# res_v2.net
KiCad netlist of a schematic drawn in EAGLE
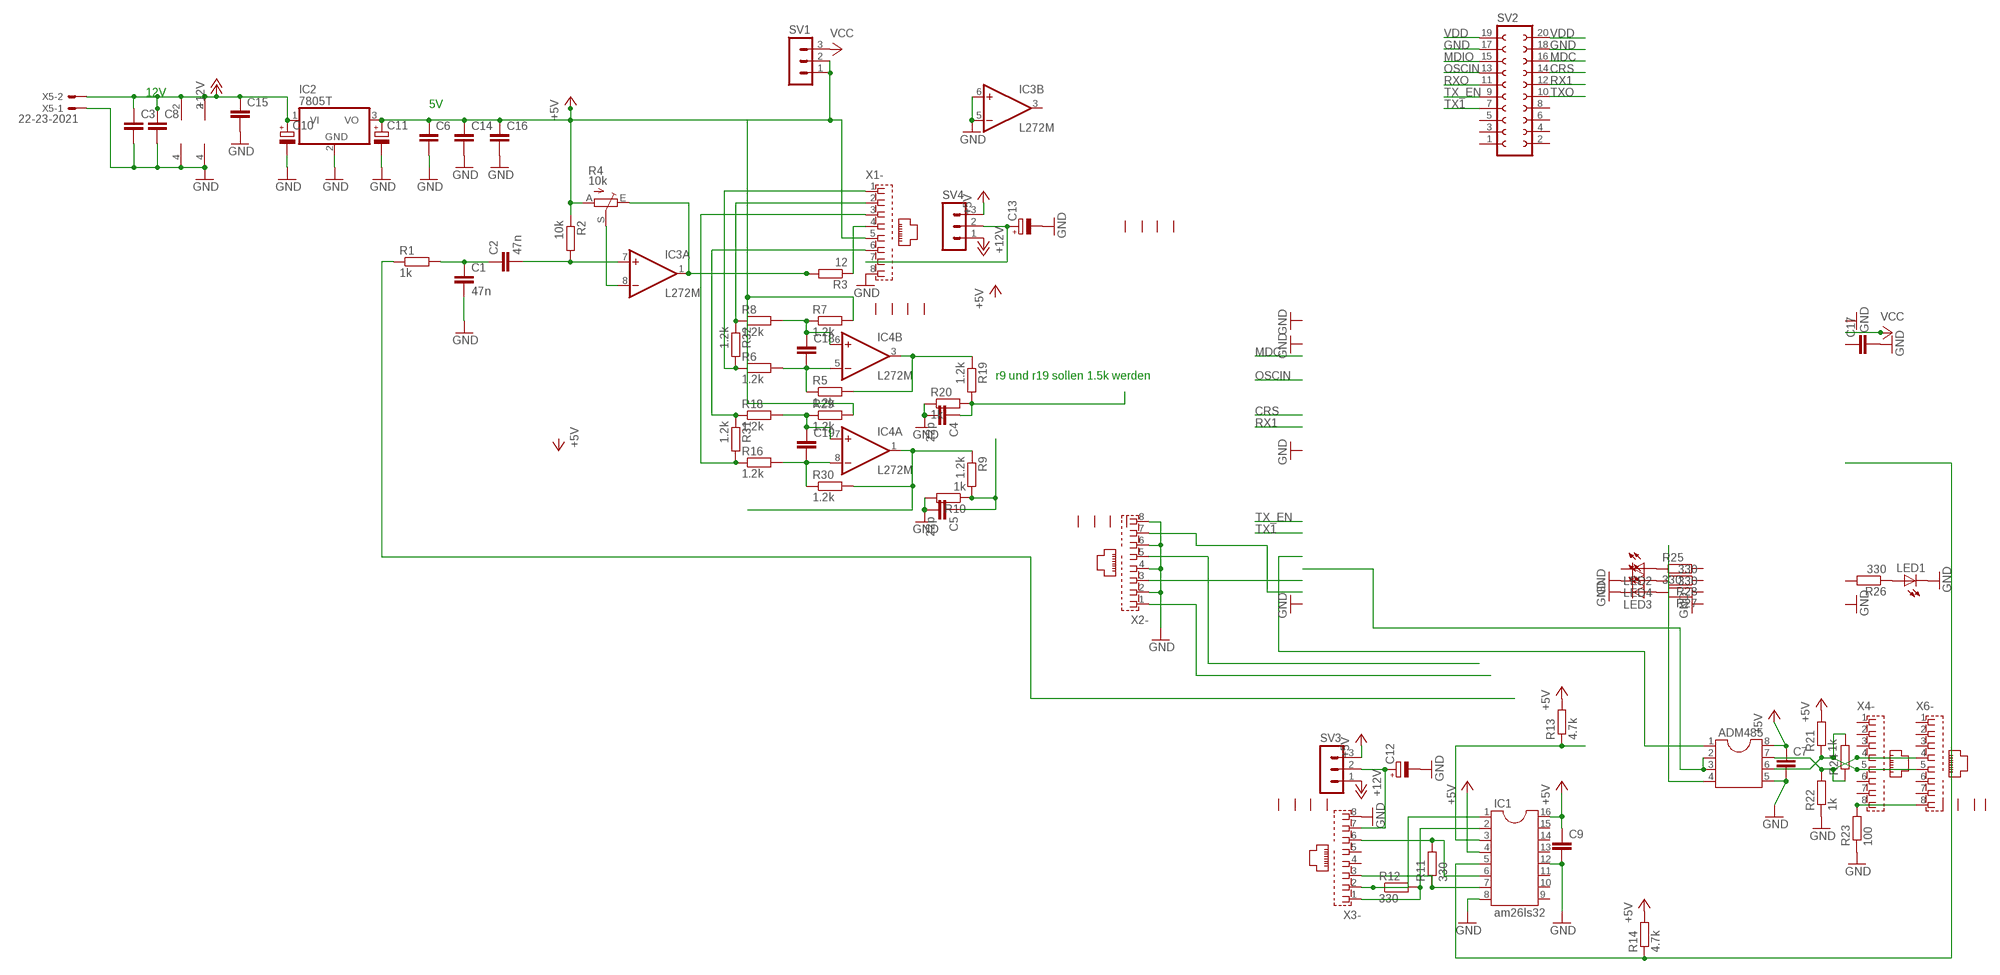
[diagram p0: schematic, sheet 1]

(export (version "E")
  (design (tool "Eeschema 10.0.6"))
  (components
    (comp (ref "ADM485")
      (value "DIL8")
      (footprint "eagle-import:DIL08")
      (libsource (lib "eagle-import") (part "DIL8"))
    )
    (comp (ref "C1")
      (value "47n")
      (footprint "eagle-import:C050-025X075")
      (libsource (lib "eagle-import") (part "C-EU050-025X075"))
    )
    (comp (ref "C2")
      (value "47n")
      (footprint "eagle-import:C050-025X075")
      (libsource (lib "eagle-import") (part "C-EU050-025X075"))
    )
    (comp (ref "C3")
      (value "C-EU050-025X075")
      (footprint "eagle-import:C050-025X075")
      (libsource (lib "eagle-import") (part "C-EU050-025X075"))
    )
    (comp (ref "C4")
      (value "22p")
      (footprint "eagle-import:C050-025X075")
      (libsource (lib "eagle-import") (part "C-EU050-025X075"))
    )
    (comp (ref "C5")
      (value "22p")
      (footprint "eagle-import:C050-025X075")
      (libsource (lib "eagle-import") (part "C-EU050-025X075"))
    )
    (comp (ref "C6")
      (value "C-EU050-025X075")
      (footprint "eagle-import:C050-025X075")
      (libsource (lib "eagle-import") (part "C-EU050-025X075"))
    )
    (comp (ref "C7")
      (value "C-EU050-025X075")
      (footprint "eagle-import:C050-025X075")
      (libsource (lib "eagle-import") (part "C-EU050-025X075"))
    )
    (comp (ref "C8")
      (value "C-EU050-025X075")
      (footprint "eagle-import:C050-025X075")
      (libsource (lib "eagle-import") (part "C-EU050-025X075"))
    )
    (comp (ref "C9")
      (value "C-EU050-025X075")
      (footprint "eagle-import:C050-025X075")
      (libsource (lib "eagle-import") (part "C-EU050-025X075"))
    )
    (comp (ref "C10")
      (value "CPOL-EUE2.5-5")
      (footprint "eagle-import:E2,5-5")
      (libsource (lib "eagle-import") (part "CPOL-EUE2.5-5"))
    )
    (comp (ref "C11")
      (value "CPOL-EUE2.5-5")
      (footprint "eagle-import:E2,5-5")
      (libsource (lib "eagle-import") (part "CPOL-EUE2.5-5"))
    )
    (comp (ref "C12")
      (value "CPOL-EUE2.5-5")
      (footprint "eagle-import:E2,5-5")
      (libsource (lib "eagle-import") (part "CPOL-EUE2.5-5"))
    )
    (comp (ref "C13")
      (value "CPOL-EUE2.5-5")
      (footprint "eagle-import:E2,5-5")
      (libsource (lib "eagle-import") (part "CPOL-EUE2.5-5"))
    )
    (comp (ref "C14")
      (value "C-EU050-025X075")
      (footprint "eagle-import:C050-025X075")
      (libsource (lib "eagle-import") (part "C-EU050-025X075"))
    )
    (comp (ref "C15")
      (value "C-EU050-025X075")
      (footprint "eagle-import:C050-025X075")
      (libsource (lib "eagle-import") (part "C-EU050-025X075"))
    )
    (comp (ref "C16")
      (value "C-EU050-025X075")
      (footprint "eagle-import:C050-025X075")
      (libsource (lib "eagle-import") (part "C-EU050-025X075"))
    )
    (comp (ref "C17")
      (value "C-EU050-025X075")
      (footprint "eagle-import:C050-025X075")
      (libsource (lib "eagle-import") (part "C-EU050-025X075"))
    )
    (comp (ref "C18")
      (value "C-EU050-025X075")
      (footprint "eagle-import:C050-025X075")
      (libsource (lib "eagle-import") (part "C-EU050-025X075"))
    )
    (comp (ref "C19")
      (value "C-EU050-025X075")
      (footprint "eagle-import:C050-025X075")
      (libsource (lib "eagle-import") (part "C-EU050-025X075"))
    )
    (comp (ref "IC1")
      (value "am26ls32")
      (footprint "eagle-import:DIL16")
      (libsource (lib "eagle-import") (part "DIL16"))
    )
    (comp (ref "IC2")
      (value "7805T")
      (footprint "eagle-import:TO220H")
      (libsource (lib "eagle-import") (part "78T05"))
    )
    (comp (ref "IC3")
      (value "L272M")
      (footprint "eagle-import:DIL08")
      (libsource (lib "eagle-import") (part "L272M"))
    )
    (comp (ref "IC4")
      (value "L272M")
      (footprint "eagle-import:DIL08")
      (libsource (lib "eagle-import") (part "L272M"))
    )
    (comp (ref "LED1")
      (value "LED3MM")
      (footprint "eagle-import:LED3MM")
      (libsource (lib "eagle-import") (part "LED3MM"))
    )
    (comp (ref "LED2")
      (value "LED3MM")
      (footprint "eagle-import:LED3MM")
      (libsource (lib "eagle-import") (part "LED3MM"))
    )
    (comp (ref "LED3")
      (value "LED3MM")
      (footprint "eagle-import:LED3MM")
      (libsource (lib "eagle-import") (part "LED3MM"))
    )
    (comp (ref "LED4")
      (value "LED3MM")
      (footprint "eagle-import:LED3MM")
      (libsource (lib "eagle-import") (part "LED3MM"))
    )
    (comp (ref "R1")
      (value "1k")
      (footprint "eagle-import:0204_7")
      (libsource (lib "eagle-import") (part "R-EU_0204/7"))
    )
    (comp (ref "R2")
      (value "10k")
      (footprint "eagle-import:0204_7")
      (libsource (lib "eagle-import") (part "R-EU_0204/7"))
    )
    (comp (ref "R3")
      (value "12")
      (footprint "eagle-import:0204_7")
      (libsource (lib "eagle-import") (part "R-EU_0204/7"))
    )
    (comp (ref "R4")
      (value "10k")
      (footprint "eagle-import:CA6V")
      (libsource (lib "eagle-import") (part "TRIM_EU-CA6V"))
    )
    (comp (ref "R5")
      (value "1.2k")
      (footprint "eagle-import:0204_7")
      (libsource (lib "eagle-import") (part "R-EU_0204/7"))
    )
    (comp (ref "R6")
      (value "1.2k")
      (footprint "eagle-import:0204_7")
      (libsource (lib "eagle-import") (part "R-EU_0204/7"))
    )
    (comp (ref "R7")
      (value "1.2k")
      (footprint "eagle-import:0204_7")
      (libsource (lib "eagle-import") (part "R-EU_0204/7"))
    )
    (comp (ref "R8")
      (value "1.2k")
      (footprint "eagle-import:0204_7")
      (libsource (lib "eagle-import") (part "R-EU_0204/7"))
    )
    (comp (ref "R9")
      (value "1.2k")
      (footprint "eagle-import:0204_7")
      (libsource (lib "eagle-import") (part "R-EU_0204/7"))
    )
    (comp (ref "R10")
      (value "1k")
      (footprint "eagle-import:0204_7")
      (libsource (lib "eagle-import") (part "R-EU_0204/7"))
    )
    (comp (ref "R11")
      (value "330")
      (footprint "eagle-import:0204_7")
      (libsource (lib "eagle-import") (part "R-EU_0204/7"))
    )
    (comp (ref "R12")
      (value "330")
      (footprint "eagle-import:0204_7")
      (libsource (lib "eagle-import") (part "R-EU_0204/7"))
    )
    (comp (ref "R13")
      (value "4.7k")
      (footprint "eagle-import:0204_7")
      (libsource (lib "eagle-import") (part "R-EU_0204/7"))
    )
    (comp (ref "R14")
      (value "4.7k")
      (footprint "eagle-import:0204_7")
      (libsource (lib "eagle-import") (part "R-EU_0204/7"))
    )
    (comp (ref "R16")
      (value "1.2k")
      (footprint "eagle-import:0204_7")
      (libsource (lib "eagle-import") (part "R-EU_0204/7"))
    )
    (comp (ref "R18")
      (value "1.2k")
      (footprint "eagle-import:0204_7")
      (libsource (lib "eagle-import") (part "R-EU_0204/7"))
    )
    (comp (ref "R19")
      (value "1.2k")
      (footprint "eagle-import:0204_7")
      (libsource (lib "eagle-import") (part "R-EU_0204/7"))
    )
    (comp (ref "R20")
      (value "1k")
      (footprint "eagle-import:0204_7")
      (libsource (lib "eagle-import") (part "R-EU_0204/7"))
    )
    (comp (ref "R21")
      (value "1k")
      (footprint "eagle-import:0204_7")
      (libsource (lib "eagle-import") (part "R-EU_0204/7"))
    )
    (comp (ref "R22")
      (value "1k")
      (footprint "eagle-import:0204_7")
      (libsource (lib "eagle-import") (part "R-EU_0204/7"))
    )
    (comp (ref "R23")
      (value "100")
      (footprint "eagle-import:0204_7")
      (libsource (lib "eagle-import") (part "R-EU_0204/7"))
    )
    (comp (ref "R24")
      (value "R-EU_0204/7")
      (footprint "eagle-import:0204_7")
      (libsource (lib "eagle-import") (part "R-EU_0204/7"))
    )
    (comp (ref "R25")
      (value "330")
      (footprint "eagle-import:0204_7")
      (libsource (lib "eagle-import") (part "R-EU_0204/7"))
    )
    (comp (ref "R26")
      (value "330")
      (footprint "eagle-import:0204_7")
      (libsource (lib "eagle-import") (part "R-EU_0204/7"))
    )
    (comp (ref "R27")
      (value "330")
      (footprint "eagle-import:0204_7")
      (libsource (lib "eagle-import") (part "R-EU_0204/7"))
    )
    (comp (ref "R28")
      (value "330")
      (footprint "eagle-import:0204_7")
      (libsource (lib "eagle-import") (part "R-EU_0204/7"))
    )
    (comp (ref "R29")
      (value "1.2k")
      (footprint "eagle-import:0204_7")
      (libsource (lib "eagle-import") (part "R-EU_0204/7"))
    )
    (comp (ref "R30")
      (value "1.2k")
      (footprint "eagle-import:0204_7")
      (libsource (lib "eagle-import") (part "R-EU_0204/7"))
    )
    (comp (ref "R31")
      (value "1.2k")
      (footprint "eagle-import:0204_7")
      (libsource (lib "eagle-import") (part "R-EU_0204/7"))
    )
    (comp (ref "R32")
      (value "1.2k")
      (footprint "eagle-import:0204_7")
      (libsource (lib "eagle-import") (part "R-EU_0204/7"))
    )
    (comp (ref "SV1")
      (value "MA03-1")
      (footprint "eagle-import:MA03-1")
      (libsource (lib "eagle-import") (part "MA03-1"))
    )
    (comp (ref "SV2")
      (value "FE10-2W")
      (footprint "eagle-import:FE10-2W")
      (libsource (lib "eagle-import") (part "FE10-2W"))
    )
    (comp (ref "SV3")
      (value "MA03-1")
      (footprint "eagle-import:MA03-1")
      (libsource (lib "eagle-import") (part "MA03-1"))
    )
    (comp (ref "SV4")
      (value "MA03-1")
      (footprint "eagle-import:MA03-1")
      (libsource (lib "eagle-import") (part "MA03-1"))
    )
    (comp (ref "X1")
      (value "RJ45")
      (footprint "eagle-import:RJ45")
      (libsource (lib "eagle-import") (part "RJ45"))
    )
    (comp (ref "X2")
      (value "RJ45")
      (footprint "eagle-import:RJ45")
      (libsource (lib "eagle-import") (part "RJ45"))
    )
    (comp (ref "X3")
      (value "RJ45")
      (footprint "eagle-import:RJ45")
      (libsource (lib "eagle-import") (part "RJ45"))
    )
    (comp (ref "X4")
      (value "RJ45")
      (footprint "eagle-import:RJ45")
      (libsource (lib "eagle-import") (part "RJ45"))
    )
    (comp (ref "X5")
      (value "22-23-2021")
      (footprint "eagle-import:22-23-2021")
      (fields (field (name "MF") "MOLEX"))
      (libsource (lib "eagle-import") (part "22-23-2021"))
    )
    (comp (ref "X6")
      (value "RJ45")
      (footprint "eagle-import:RJ45")
      (libsource (lib "eagle-import") (part "RJ45"))
    )
  )
  (nets
    (net (code "1") (name "+5V") (class "Default")
      (node (ref "ADM485") (pin "8") (pinfunction "8_8") (pintype "passive"))
      (node (ref "C11") (pin "+") (pinfunction "+_+") (pintype "passive"))
      (node (ref "C14") (pin "1") (pinfunction "1_1") (pintype "passive"))
      (node (ref "C16") (pin "1") (pinfunction "1_1") (pintype "passive"))
      (node (ref "C6") (pin "1") (pinfunction "1_1") (pintype "passive"))
      (node (ref "C7") (pin "1") (pinfunction "1_1") (pintype "passive"))
      (node (ref "C9") (pin "1") (pinfunction "1_1") (pintype "passive"))
      (node (ref "IC1") (pin "16") (pinfunction "16_16") (pintype "passive"))
      (node (ref "IC1") (pin "4") (pinfunction "4_4") (pintype "passive"))
      (node (ref "IC2") (pin "3") (pinfunction "VO_3") (pintype "passive"))
      (node (ref "R13") (pin "2") (pinfunction "2_2") (pintype "passive"))
      (node (ref "R14") (pin "2") (pinfunction "2_2") (pintype "passive"))
      (node (ref "R2") (pin "1") (pinfunction "1_1") (pintype "passive"))
      (node (ref "R21") (pin "2") (pinfunction "2_2") (pintype "passive"))
      (node (ref "R29") (pin "2") (pinfunction "2_2") (pintype "passive"))
      (node (ref "R4") (pin "A") (pinfunction "A_A") (pintype "passive"))
      (node (ref "R7") (pin "2") (pinfunction "2_2") (pintype "passive"))
      (node (ref "SV3") (pin "3") (pinfunction "3_3") (pintype "passive"))
      (node (ref "SV4") (pin "3") (pinfunction "3_3") (pintype "passive"))
    )
    (net (code "2") (name "+12V") (class "Default")
      (node (ref "C10") (pin "+") (pinfunction "+_+") (pintype "passive"))
      (node (ref "C15") (pin "1") (pinfunction "1_1") (pintype "passive"))
      (node (ref "C3") (pin "1") (pinfunction "1_1") (pintype "passive"))
      (node (ref "C8") (pin "1") (pinfunction "1_1") (pintype "passive"))
      (node (ref "IC2") (pin "1") (pinfunction "VI_1") (pintype "input"))
      (node (ref "IC3") (pin "2") (pinfunction "V+_2") (pintype "power_in"))
      (node (ref "IC4") (pin "2") (pinfunction "V+_2") (pintype "power_in"))
      (node (ref "SV3") (pin "1") (pinfunction "1_1") (pintype "passive"))
      (node (ref "SV4") (pin "1") (pinfunction "1_1") (pintype "passive"))
      (node (ref "X5") (pin "2") (pinfunction "S_2") (pintype "passive"))
    )
    (net (code "3") (name "/CRS") (class "Default")
      (node (ref "SV2") (pin "14") (pinfunction "14_14") (pintype "passive"))
    )
    (net (code "4") (name "/MDC") (class "Default")
      (node (ref "SV2") (pin "16") (pinfunction "16_16") (pintype "passive"))
    )
    (net (code "5") (name "/MDIO") (class "Default")
      (node (ref "SV2") (pin "15") (pinfunction "15_15") (pintype "passive"))
    )
    (net (code "6") (name "/OSCIN") (class "Default")
      (node (ref "SV2") (pin "13") (pinfunction "13_13") (pintype "passive"))
    )
    (net (code "7") (name "/RX1") (class "Default")
      (node (ref "SV2") (pin "12") (pinfunction "12_12") (pintype "passive"))
    )
    (net (code "8") (name "/RXO") (class "Default")
      (node (ref "SV2") (pin "11") (pinfunction "11_11") (pintype "passive"))
    )
    (net (code "9") (name "/TX1") (class "Default")
      (node (ref "SV2") (pin "7") (pinfunction "7_7") (pintype "passive"))
    )
    (net (code "10") (name "/TXO") (class "Default")
      (node (ref "SV2") (pin "10") (pinfunction "10_10") (pintype "passive"))
    )
    (net (code "11") (name "/TX_EN") (class "Default")
      (node (ref "SV2") (pin "9") (pinfunction "9_9") (pintype "passive"))
    )
    (net (code "12") (name "/VDD") (class "Default")
      (node (ref "SV2") (pin "19") (pinfunction "19_19") (pintype "passive"))
      (node (ref "SV2") (pin "20") (pinfunction "20_20") (pintype "passive"))
    )
    (net (code "13") (name "GND") (class "Default")
      (node (ref "ADM485") (pin "5") (pinfunction "5_5") (pintype "passive"))
      (node (ref "C1") (pin "2") (pinfunction "2_2") (pintype "passive"))
      (node (ref "C10") (pin "-") (pinfunction "-_-") (pintype "passive"))
      (node (ref "C11") (pin "-") (pinfunction "-_-") (pintype "passive"))
      (node (ref "C12") (pin "-") (pinfunction "-_-") (pintype "passive"))
      (node (ref "C13") (pin "-") (pinfunction "-_-") (pintype "passive"))
      (node (ref "C14") (pin "2") (pinfunction "2_2") (pintype "passive"))
      (node (ref "C15") (pin "2") (pinfunction "2_2") (pintype "passive"))
      (node (ref "C16") (pin "2") (pinfunction "2_2") (pintype "passive"))
      (node (ref "C17") (pin "2") (pinfunction "2_2") (pintype "passive"))
      (node (ref "C3") (pin "2") (pinfunction "2_2") (pintype "passive"))
      (node (ref "C4") (pin "2") (pinfunction "2_2") (pintype "passive"))
      (node (ref "C5") (pin "2") (pinfunction "2_2") (pintype "passive"))
      (node (ref "C6") (pin "2") (pinfunction "2_2") (pintype "passive"))
      (node (ref "C7") (pin "2") (pinfunction "2_2") (pintype "passive"))
      (node (ref "C8") (pin "2") (pinfunction "2_2") (pintype "passive"))
      (node (ref "C9") (pin "2") (pinfunction "2_2") (pintype "passive"))
      (node (ref "IC1") (pin "12") (pinfunction "12_12") (pintype "passive"))
      (node (ref "IC1") (pin "8") (pinfunction "8_8") (pintype "passive"))
      (node (ref "IC2") (pin "2") (pinfunction "GND_2") (pintype "passive"))
      (node (ref "IC3") (pin "4") (pinfunction "GND_4") (pintype "power_in"))
      (node (ref "IC3") (pin "5") (pinfunction "-IN_5") (pintype "input"))
      (node (ref "IC3") (pin "6") (pinfunction "+IN_6") (pintype "input"))
      (node (ref "IC4") (pin "4") (pinfunction "GND_4") (pintype "power_in"))
      (node (ref "LED1") (pin "K") (pinfunction "C_K") (pintype "passive"))
      (node (ref "LED3") (pin "K") (pinfunction "C_K") (pintype "passive"))
      (node (ref "LED4") (pin "K") (pinfunction "C_K") (pintype "passive"))
      (node (ref "R10") (pin "2") (pinfunction "2_2") (pintype "passive"))
      (node (ref "R20") (pin "1") (pinfunction "1_1") (pintype "passive"))
      (node (ref "R22") (pin "1") (pinfunction "1_1") (pintype "passive"))
      (node (ref "R23") (pin "1") (pinfunction "1_1") (pintype "passive"))
      (node (ref "SV2") (pin "17") (pinfunction "17_17") (pintype "passive"))
      (node (ref "SV2") (pin "18") (pinfunction "18_18") (pintype "passive"))
      (node (ref "X1") (pin "8") (pinfunction "8_8") (pintype "passive"))
      (node (ref "X2") (pin "2") (pinfunction "2_2") (pintype "passive"))
      (node (ref "X2") (pin "4") (pinfunction "4_4") (pintype "passive"))
      (node (ref "X2") (pin "6") (pinfunction "6_6") (pintype "passive"))
      (node (ref "X2") (pin "8") (pinfunction "8_8") (pintype "passive"))
      (node (ref "X3") (pin "8") (pinfunction "8_8") (pintype "passive"))
      (node (ref "X5") (pin "1") (pinfunction "S_1") (pintype "passive"))
    )
    (net (code "14") (name "Net-(ADM485-Pad2)") (class "Default")
      (node (ref "ADM485") (pin "2") (pinfunction "2_2") (pintype "passive"))
      (node (ref "ADM485") (pin "3") (pinfunction "3_3") (pintype "passive"))
    )
    (net (code "15") (name "Net-(ADM485-Pad6)") (class "Default")
      (node (ref "ADM485") (pin "6") (pinfunction "6_6") (pintype "passive"))
      (node (ref "R21") (pin "1") (pinfunction "1_1") (pintype "passive"))
      (node (ref "R24") (pin "2") (pinfunction "2_2") (pintype "passive"))
      (node (ref "X4") (pin "5") (pinfunction "5_5") (pintype "passive"))
      (node (ref "X6") (pin "5") (pinfunction "5_5") (pintype "passive"))
    )
    (net (code "16") (name "Net-(ADM485-Pad7)") (class "Default")
      (node (ref "ADM485") (pin "7") (pinfunction "7_7") (pintype "passive"))
      (node (ref "R22") (pin "2") (pinfunction "2_2") (pintype "passive"))
      (node (ref "R24") (pin "1") (pinfunction "1_1") (pintype "passive"))
      (node (ref "X4") (pin "4") (pinfunction "4_4") (pintype "passive"))
      (node (ref "X6") (pin "4") (pinfunction "4_4") (pintype "passive"))
    )
    (net (code "17") (name "Net-(C1-Pad1)") (class "Default")
      (node (ref "C1") (pin "1") (pinfunction "1_1") (pintype "passive"))
      (node (ref "C2") (pin "1") (pinfunction "1_1") (pintype "passive"))
      (node (ref "R1") (pin "2") (pinfunction "2_2") (pintype "passive"))
    )
    (net (code "18") (name "Net-(C4-Pad1)") (class "Default")
      (node (ref "C4") (pin "1") (pinfunction "1_1") (pintype "passive"))
      (node (ref "R19") (pin "2") (pinfunction "2_2") (pintype "passive"))
      (node (ref "R20") (pin "2") (pinfunction "2_2") (pintype "passive"))
    )
    (net (code "19") (name "Net-(C5-Pad1)") (class "Default")
      (node (ref "C5") (pin "1") (pinfunction "1_1") (pintype "passive"))
      (node (ref "R10") (pin "1") (pinfunction "1_1") (pintype "passive"))
      (node (ref "R9") (pin "2") (pinfunction "2_2") (pintype "passive"))
    )
    (net (code "20") (name "Net-(C12-Pad+)") (class "Default")
      (node (ref "C12") (pin "+") (pinfunction "+_+") (pintype "passive"))
      (node (ref "SV3") (pin "2") (pinfunction "2_2") (pintype "passive"))
      (node (ref "X3") (pin "7") (pinfunction "7_7") (pintype "passive"))
    )
    (net (code "21") (name "Net-(C13-Pad+)") (class "Default")
      (node (ref "C13") (pin "+") (pinfunction "+_+") (pintype "passive"))
      (node (ref "SV4") (pin "2") (pinfunction "2_2") (pintype "passive"))
      (node (ref "X1") (pin "7") (pinfunction "7_7") (pintype "passive"))
    )
    (net (code "22") (name "Net-(IC1-Pad1)") (class "Default")
      (node (ref "IC1") (pin "1") (pinfunction "1_1") (pintype "passive"))
      (node (ref "R12") (pin "1") (pinfunction "1_1") (pintype "passive"))
      (node (ref "X3") (pin "2") (pinfunction "2_2") (pintype "passive"))
    )
    (net (code "23") (name "Net-(IC1-Pad2)") (class "Default")
      (node (ref "IC1") (pin "2") (pinfunction "2_2") (pintype "passive"))
      (node (ref "R12") (pin "2") (pinfunction "2_2") (pintype "passive"))
      (node (ref "X3") (pin "1") (pinfunction "1_1") (pintype "passive"))
    )
    (net (code "24") (name "Net-(IC1-Pad3)") (class "Default")
      (node (ref "IC1") (pin "3") (pinfunction "3_3") (pintype "passive"))
      (node (ref "R13") (pin "1") (pinfunction "1_1") (pintype "passive"))
    )
    (net (code "25") (name "Net-(IC1-Pad5)") (class "Default")
      (node (ref "IC1") (pin "5") (pinfunction "5_5") (pintype "passive"))
      (node (ref "R14") (pin "1") (pinfunction "1_1") (pintype "passive"))
    )
    (net (code "26") (name "Net-(IC1-Pad6)") (class "Default")
      (node (ref "IC1") (pin "6") (pinfunction "6_6") (pintype "passive"))
      (node (ref "R11") (pin "2") (pinfunction "2_2") (pintype "passive"))
      (node (ref "X3") (pin "6") (pinfunction "6_6") (pintype "passive"))
    )
    (net (code "27") (name "Net-(IC1-Pad7)") (class "Default")
      (node (ref "IC1") (pin "7") (pinfunction "7_7") (pintype "passive"))
      (node (ref "R11") (pin "1") (pinfunction "1_1") (pintype "passive"))
      (node (ref "X3") (pin "3") (pinfunction "3_3") (pintype "passive"))
    )
    (net (code "28") (name "Net-(IC3A-+IN)") (class "Default")
      (node (ref "C2") (pin "2") (pinfunction "2_2") (pintype "passive"))
      (node (ref "IC3") (pin "7") (pinfunction "+IN_7") (pintype "input"))
      (node (ref "R2") (pin "2") (pinfunction "2_2") (pintype "passive"))
    )
    (net (code "29") (name "Net-(IC3A--IN)") (class "Default")
      (node (ref "IC3") (pin "8") (pinfunction "-IN_8") (pintype "input"))
      (node (ref "R4") (pin "S") (pinfunction "S_S") (pintype "passive"))
    )
    (net (code "30") (name "Net-(IC3A-OUT)") (class "Default")
      (node (ref "IC3") (pin "1") (pinfunction "OUT_1") (pintype "output"))
      (node (ref "R3") (pin "2") (pinfunction "2_2") (pintype "passive"))
      (node (ref "R4") (pin "E") (pinfunction "E_E") (pintype "passive"))
    )
    (net (code "31") (name "Net-(IC4A-+IN)") (class "Default")
      (node (ref "C19") (pin "1") (pinfunction "1_1") (pintype "passive"))
      (node (ref "IC4") (pin "7") (pinfunction "+IN_7") (pintype "input"))
      (node (ref "R18") (pin "2") (pinfunction "2_2") (pintype "passive"))
      (node (ref "R29") (pin "1") (pinfunction "1_1") (pintype "passive"))
    )
    (net (code "32") (name "Net-(IC4A--IN)") (class "Default")
      (node (ref "C19") (pin "2") (pinfunction "2_2") (pintype "passive"))
      (node (ref "IC4") (pin "8") (pinfunction "-IN_8") (pintype "input"))
      (node (ref "R16") (pin "2") (pinfunction "2_2") (pintype "passive"))
      (node (ref "R30") (pin "1") (pinfunction "1_1") (pintype "passive"))
    )
    (net (code "33") (name "Net-(IC4A-OUT)") (class "Default")
      (node (ref "IC4") (pin "1") (pinfunction "OUT_1") (pintype "output"))
      (node (ref "R30") (pin "2") (pinfunction "2_2") (pintype "passive"))
      (node (ref "R9") (pin "1") (pinfunction "1_1") (pintype "passive"))
    )
    (net (code "34") (name "Net-(IC4B-+IN)") (class "Default")
      (node (ref "C18") (pin "1") (pinfunction "1_1") (pintype "passive"))
      (node (ref "IC4") (pin "6") (pinfunction "+IN_6") (pintype "input"))
      (node (ref "R7") (pin "1") (pinfunction "1_1") (pintype "passive"))
      (node (ref "R8") (pin "2") (pinfunction "2_2") (pintype "passive"))
    )
    (net (code "35") (name "Net-(IC4B--IN)") (class "Default")
      (node (ref "C18") (pin "2") (pinfunction "2_2") (pintype "passive"))
      (node (ref "IC4") (pin "5") (pinfunction "-IN_5") (pintype "input"))
      (node (ref "R5") (pin "1") (pinfunction "1_1") (pintype "passive"))
      (node (ref "R6") (pin "2") (pinfunction "2_2") (pintype "passive"))
    )
    (net (code "36") (name "Net-(IC4B-OUT)") (class "Default")
      (node (ref "IC4") (pin "3") (pinfunction "OUT_3") (pintype "output"))
      (node (ref "R19") (pin "1") (pinfunction "1_1") (pintype "passive"))
      (node (ref "R5") (pin "2") (pinfunction "2_2") (pintype "passive"))
    )
    (net (code "37") (name "Net-(LED1-PadA)") (class "Default")
      (node (ref "LED1") (pin "A") (pinfunction "A_A") (pintype "passive"))
      (node (ref "R26") (pin "1") (pinfunction "1_1") (pintype "passive"))
    )
    (net (code "38") (name "Net-(LED2-PadA)") (class "Default")
      (node (ref "LED2") (pin "A") (pinfunction "A_A") (pintype "passive"))
      (node (ref "R25") (pin "1") (pinfunction "1_1") (pintype "passive"))
    )
    (net (code "39") (name "Net-(LED3-PadA)") (class "Default")
      (node (ref "LED3") (pin "A") (pinfunction "A_A") (pintype "passive"))
      (node (ref "R27") (pin "2") (pinfunction "2_2") (pintype "passive"))
    )
    (net (code "40") (name "Net-(LED4-PadA)") (class "Default")
      (node (ref "LED4") (pin "A") (pinfunction "A_A") (pintype "passive"))
      (node (ref "R28") (pin "2") (pinfunction "2_2") (pintype "passive"))
    )
    (net (code "41") (name "Net-(R3-Pad1)") (class "Default")
      (node (ref "R3") (pin "1") (pinfunction "1_1") (pintype "passive"))
      (node (ref "X1") (pin "4") (pinfunction "4_4") (pintype "passive"))
    )
    (net (code "42") (name "Net-(R16-Pad1)") (class "Default")
      (node (ref "R16") (pin "1") (pinfunction "1_1") (pintype "passive"))
      (node (ref "R31") (pin "2") (pinfunction "2_2") (pintype "passive"))
      (node (ref "X1") (pin "3") (pinfunction "3_3") (pintype "passive"))
    )
    (net (code "43") (name "Net-(R18-Pad1)") (class "Default")
      (node (ref "R18") (pin "1") (pinfunction "1_1") (pintype "passive"))
      (node (ref "R31") (pin "1") (pinfunction "1_1") (pintype "passive"))
      (node (ref "X1") (pin "6") (pinfunction "6_6") (pintype "passive"))
    )
    (net (code "44") (name "Net-(R23-Pad2)") (class "Default")
      (node (ref "R23") (pin "2") (pinfunction "2_2") (pintype "passive"))
      (node (ref "X4") (pin "8") (pinfunction "8_8") (pintype "passive"))
      (node (ref "X6") (pin "8") (pinfunction "8_8") (pintype "passive"))
    )
    (net (code "45") (name "Net-(R32-Pad1)") (class "Default")
      (node (ref "R32") (pin "1") (pinfunction "1_1") (pintype "passive"))
      (node (ref "R8") (pin "1") (pinfunction "1_1") (pintype "passive"))
      (node (ref "X1") (pin "2") (pinfunction "2_2") (pintype "passive"))
    )
    (net (code "46") (name "Net-(R32-Pad2)") (class "Default")
      (node (ref "R32") (pin "2") (pinfunction "2_2") (pintype "passive"))
      (node (ref "R6") (pin "1") (pinfunction "1_1") (pintype "passive"))
      (node (ref "X1") (pin "1") (pinfunction "1_1") (pintype "passive"))
    )
    (net (code "47") (name "Net-(SV1-Pad1)") (class "Default")
      (node (ref "SV1") (pin "1") (pinfunction "1_1") (pintype "passive"))
      (node (ref "SV1") (pin "2") (pinfunction "2_2") (pintype "passive"))
      (node (ref "X1") (pin "5") (pinfunction "5_5") (pintype "passive"))
    )
    (net (code "48") (name "VCC") (class "Default")
      (node (ref "SV1") (pin "3") (pinfunction "3_3") (pintype "passive"))
    )
    (net (code "49") (name "unconnected-(ADM485-Pad1)") (class "Default")
      (node (ref "ADM485") (pin "1") (pinfunction "1_1") (pintype "passive"))
    )
    (net (code "50") (name "unconnected-(ADM485-Pad4)") (class "Default")
      (node (ref "ADM485") (pin "4") (pinfunction "4_4") (pintype "passive"))
    )
    (net (code "51") (name "unconnected-(C17-Pad1)") (class "Default")
      (node (ref "C17") (pin "1") (pinfunction "1_1") (pintype "passive"))
    )
    (net (code "52") (name "unconnected-(IC1-Pad9)") (class "Default")
      (node (ref "IC1") (pin "9") (pinfunction "9_9") (pintype "passive"))
    )
    (net (code "53") (name "unconnected-(IC1-Pad10)") (class "Default")
      (node (ref "IC1") (pin "10") (pinfunction "10_10") (pintype "passive"))
    )
    (net (code "54") (name "unconnected-(IC1-Pad11)") (class "Default")
      (node (ref "IC1") (pin "11") (pinfunction "11_11") (pintype "passive"))
    )
    (net (code "55") (name "unconnected-(IC1-Pad13)") (class "Default")
      (node (ref "IC1") (pin "13") (pinfunction "13_13") (pintype "passive"))
    )
    (net (code "56") (name "unconnected-(IC1-Pad14)") (class "Default")
      (node (ref "IC1") (pin "14") (pinfunction "14_14") (pintype "passive"))
    )
    (net (code "57") (name "unconnected-(IC1-Pad15)") (class "Default")
      (node (ref "IC1") (pin "15") (pinfunction "15_15") (pintype "passive"))
    )
    (net (code "58") (name "unconnected-(IC3B-OUT-Pad3)") (class "Default")
      (node (ref "IC3") (pin "3") (pinfunction "OUT_3") (pintype "output"))
    )
    (net (code "59") (name "unconnected-(LED2-C-PadK)") (class "Default")
      (node (ref "LED2") (pin "K") (pinfunction "C_K") (pintype "passive"))
    )
    (net (code "60") (name "unconnected-(R1-Pad1)") (class "Default")
      (node (ref "R1") (pin "1") (pinfunction "1_1") (pintype "passive"))
    )
    (net (code "61") (name "unconnected-(R25-Pad2)") (class "Default")
      (node (ref "R25") (pin "2") (pinfunction "2_2") (pintype "passive"))
    )
    (net (code "62") (name "unconnected-(R26-Pad2)") (class "Default")
      (node (ref "R26") (pin "2") (pinfunction "2_2") (pintype "passive"))
    )
    (net (code "63") (name "unconnected-(R27-Pad1)") (class "Default")
      (node (ref "R27") (pin "1") (pinfunction "1_1") (pintype "passive"))
    )
    (net (code "64") (name "unconnected-(R28-Pad1)") (class "Default")
      (node (ref "R28") (pin "1") (pinfunction "1_1") (pintype "passive"))
    )
    (net (code "65") (name "unconnected-(SV2-Pad1)") (class "Default")
      (node (ref "SV2") (pin "1") (pinfunction "1_1") (pintype "passive"))
    )
    (net (code "66") (name "unconnected-(SV2-Pad2)") (class "Default")
      (node (ref "SV2") (pin "2") (pinfunction "2_2") (pintype "passive"))
    )
    (net (code "67") (name "unconnected-(SV2-Pad3)") (class "Default")
      (node (ref "SV2") (pin "3") (pinfunction "3_3") (pintype "passive"))
    )
    (net (code "68") (name "unconnected-(SV2-Pad4)") (class "Default")
      (node (ref "SV2") (pin "4") (pinfunction "4_4") (pintype "passive"))
    )
    (net (code "69") (name "unconnected-(SV2-Pad5)") (class "Default")
      (node (ref "SV2") (pin "5") (pinfunction "5_5") (pintype "passive"))
    )
    (net (code "70") (name "unconnected-(SV2-Pad6)") (class "Default")
      (node (ref "SV2") (pin "6") (pinfunction "6_6") (pintype "passive"))
    )
    (net (code "71") (name "unconnected-(SV2-Pad8)") (class "Default")
      (node (ref "SV2") (pin "8") (pinfunction "8_8") (pintype "passive"))
    )
    (net (code "72") (name "unconnected-(X1B-1-PadG1)") (class "Default")
      (node (ref "X1") (pin "G1") (pinfunction "1_G1") (pintype "passive"))
    )
    (net (code "73") (name "unconnected-(X1C-1-PadG2)") (class "Default")
      (node (ref "X1") (pin "G2") (pinfunction "1_G2") (pintype "passive"))
    )
    (net (code "74") (name "unconnected-(X1D-1-PadG3)") (class "Default")
      (node (ref "X1") (pin "G3") (pinfunction "1_G3") (pintype "passive"))
    )
    (net (code "75") (name "unconnected-(X1E-1-PadG4)") (class "Default")
      (node (ref "X1") (pin "G4") (pinfunction "1_G4") (pintype "passive"))
    )
    (net (code "76") (name "unconnected-(X2-Pad1)") (class "Default")
      (node (ref "X2") (pin "1") (pinfunction "1_1") (pintype "passive"))
    )
    (net (code "77") (name "unconnected-(X2-Pad3)") (class "Default")
      (node (ref "X2") (pin "3") (pinfunction "3_3") (pintype "passive"))
    )
    (net (code "78") (name "unconnected-(X2-Pad5)") (class "Default")
      (node (ref "X2") (pin "5") (pinfunction "5_5") (pintype "passive"))
    )
    (net (code "79") (name "unconnected-(X2-Pad7)") (class "Default")
      (node (ref "X2") (pin "7") (pinfunction "7_7") (pintype "passive"))
    )
    (net (code "80") (name "unconnected-(X2B-1-PadG1)") (class "Default")
      (node (ref "X2") (pin "G1") (pinfunction "1_G1") (pintype "passive"))
    )
    (net (code "81") (name "unconnected-(X2C-1-PadG2)") (class "Default")
      (node (ref "X2") (pin "G2") (pinfunction "1_G2") (pintype "passive"))
    )
    (net (code "82") (name "unconnected-(X2D-1-PadG3)") (class "Default")
      (node (ref "X2") (pin "G3") (pinfunction "1_G3") (pintype "passive"))
    )
    (net (code "83") (name "unconnected-(X2E-1-PadG4)") (class "Default")
      (node (ref "X2") (pin "G4") (pinfunction "1_G4") (pintype "passive"))
    )
    (net (code "84") (name "unconnected-(X3-Pad4)") (class "Default")
      (node (ref "X3") (pin "4") (pinfunction "4_4") (pintype "passive"))
    )
    (net (code "85") (name "unconnected-(X3-Pad5)") (class "Default")
      (node (ref "X3") (pin "5") (pinfunction "5_5") (pintype "passive"))
    )
    (net (code "86") (name "unconnected-(X3B-1-PadG1)") (class "Default")
      (node (ref "X3") (pin "G1") (pinfunction "1_G1") (pintype "passive"))
    )
    (net (code "87") (name "unconnected-(X3C-1-PadG2)") (class "Default")
      (node (ref "X3") (pin "G2") (pinfunction "1_G2") (pintype "passive"))
    )
    (net (code "88") (name "unconnected-(X3D-1-PadG3)") (class "Default")
      (node (ref "X3") (pin "G3") (pinfunction "1_G3") (pintype "passive"))
    )
    (net (code "89") (name "unconnected-(X3E-1-PadG4)") (class "Default")
      (node (ref "X3") (pin "G4") (pinfunction "1_G4") (pintype "passive"))
    )
    (net (code "90") (name "unconnected-(X4-Pad1)") (class "Default")
      (node (ref "X4") (pin "1") (pinfunction "1_1") (pintype "passive"))
    )
    (net (code "91") (name "unconnected-(X4-Pad2)") (class "Default")
      (node (ref "X4") (pin "2") (pinfunction "2_2") (pintype "passive"))
    )
    (net (code "92") (name "unconnected-(X4-Pad3)") (class "Default")
      (node (ref "X4") (pin "3") (pinfunction "3_3") (pintype "passive"))
    )
    (net (code "93") (name "unconnected-(X4-Pad6)") (class "Default")
      (node (ref "X4") (pin "6") (pinfunction "6_6") (pintype "passive"))
    )
    (net (code "94") (name "unconnected-(X4-Pad7)") (class "Default")
      (node (ref "X4") (pin "7") (pinfunction "7_7") (pintype "passive"))
    )
    (net (code "95") (name "unconnected-(X4B-1-PadG1)") (class "Default")
      (node (ref "X4") (pin "G1") (pinfunction "1_G1") (pintype "passive"))
    )
    (net (code "96") (name "unconnected-(X4C-1-PadG2)") (class "Default")
      (node (ref "X4") (pin "G2") (pinfunction "1_G2") (pintype "passive"))
    )
    (net (code "97") (name "unconnected-(X4D-1-PadG3)") (class "Default")
      (node (ref "X4") (pin "G3") (pinfunction "1_G3") (pintype "passive"))
    )
    (net (code "98") (name "unconnected-(X4E-1-PadG4)") (class "Default")
      (node (ref "X4") (pin "G4") (pinfunction "1_G4") (pintype "passive"))
    )
    (net (code "99") (name "unconnected-(X6-Pad1)") (class "Default")
      (node (ref "X6") (pin "1") (pinfunction "1_1") (pintype "passive"))
    )
    (net (code "100") (name "unconnected-(X6-Pad2)") (class "Default")
      (node (ref "X6") (pin "2") (pinfunction "2_2") (pintype "passive"))
    )
    (net (code "101") (name "unconnected-(X6-Pad3)") (class "Default")
      (node (ref "X6") (pin "3") (pinfunction "3_3") (pintype "passive"))
    )
    (net (code "102") (name "unconnected-(X6-Pad6)") (class "Default")
      (node (ref "X6") (pin "6") (pinfunction "6_6") (pintype "passive"))
    )
    (net (code "103") (name "unconnected-(X6-Pad7)") (class "Default")
      (node (ref "X6") (pin "7") (pinfunction "7_7") (pintype "passive"))
    )
    (net (code "104") (name "unconnected-(X6B-1-PadG1)") (class "Default")
      (node (ref "X6") (pin "G1") (pinfunction "1_G1") (pintype "passive"))
    )
    (net (code "105") (name "unconnected-(X6C-1-PadG2)") (class "Default")
      (node (ref "X6") (pin "G2") (pinfunction "1_G2") (pintype "passive"))
    )
    (net (code "106") (name "unconnected-(X6D-1-PadG3)") (class "Default")
      (node (ref "X6") (pin "G3") (pinfunction "1_G3") (pintype "passive"))
    )
    (net (code "107") (name "unconnected-(X6E-1-PadG4)") (class "Default")
      (node (ref "X6") (pin "G4") (pinfunction "1_G4") (pintype "passive"))
    )
  )
)
